# ESP32_with_USBC.net
KiCad netlist of a schematic drawn in Altium Designer
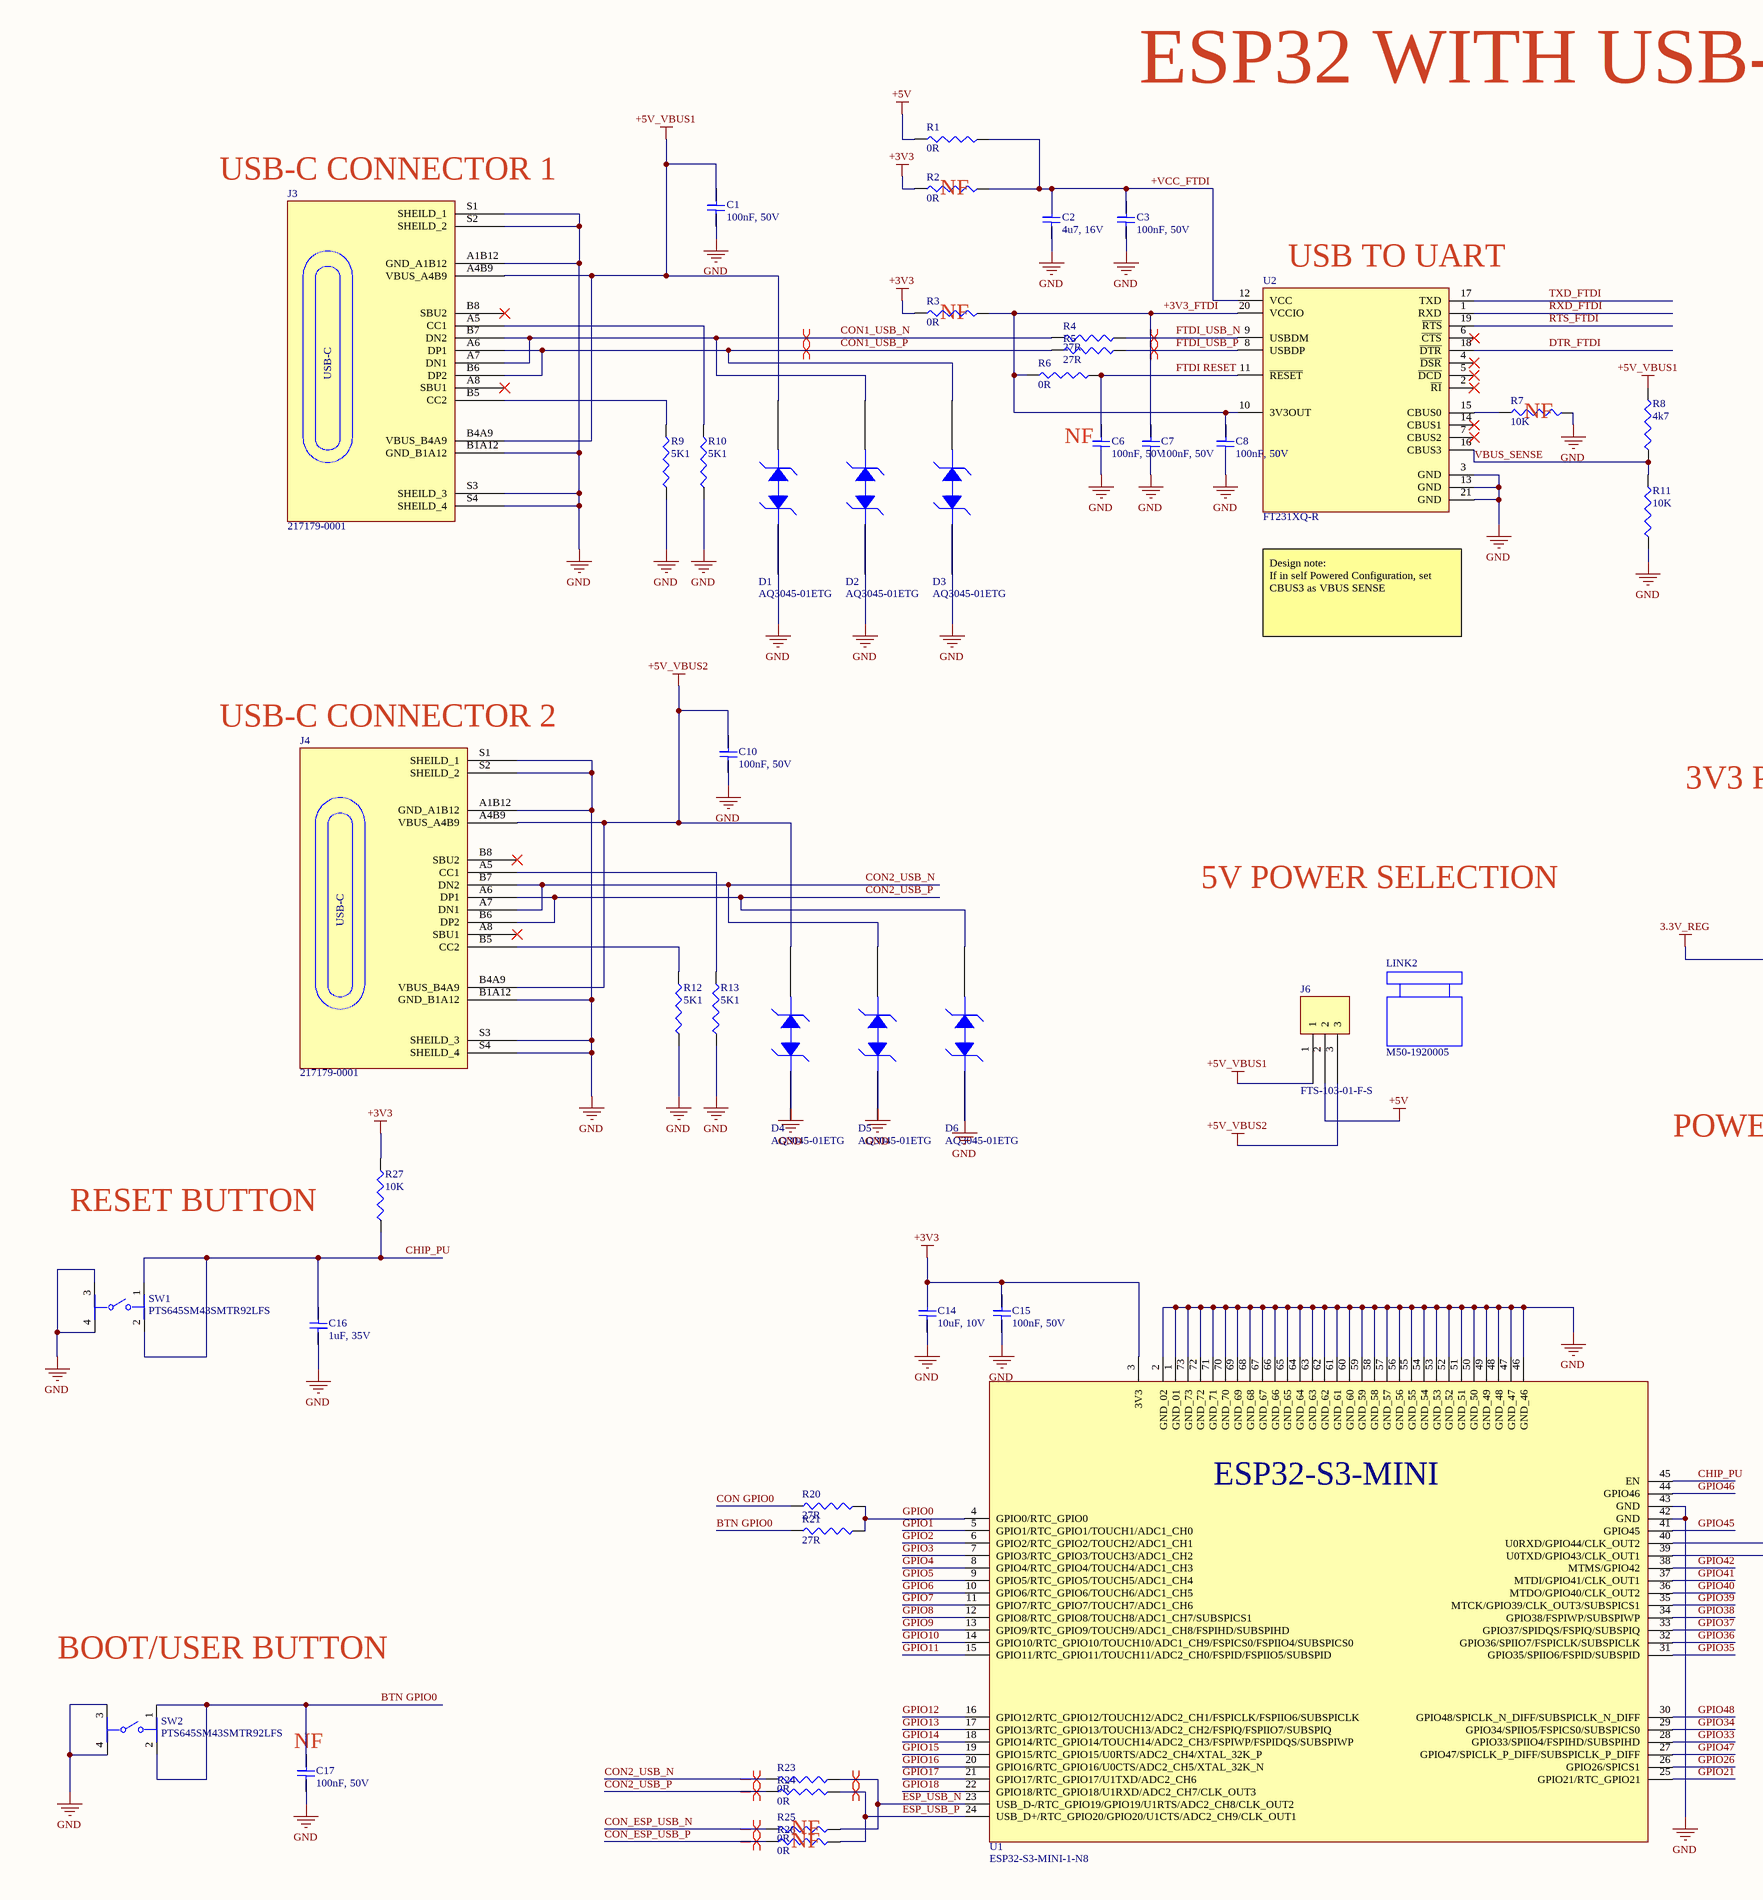
[diagram p0: ESP32 with USBC.SchDoc, left]
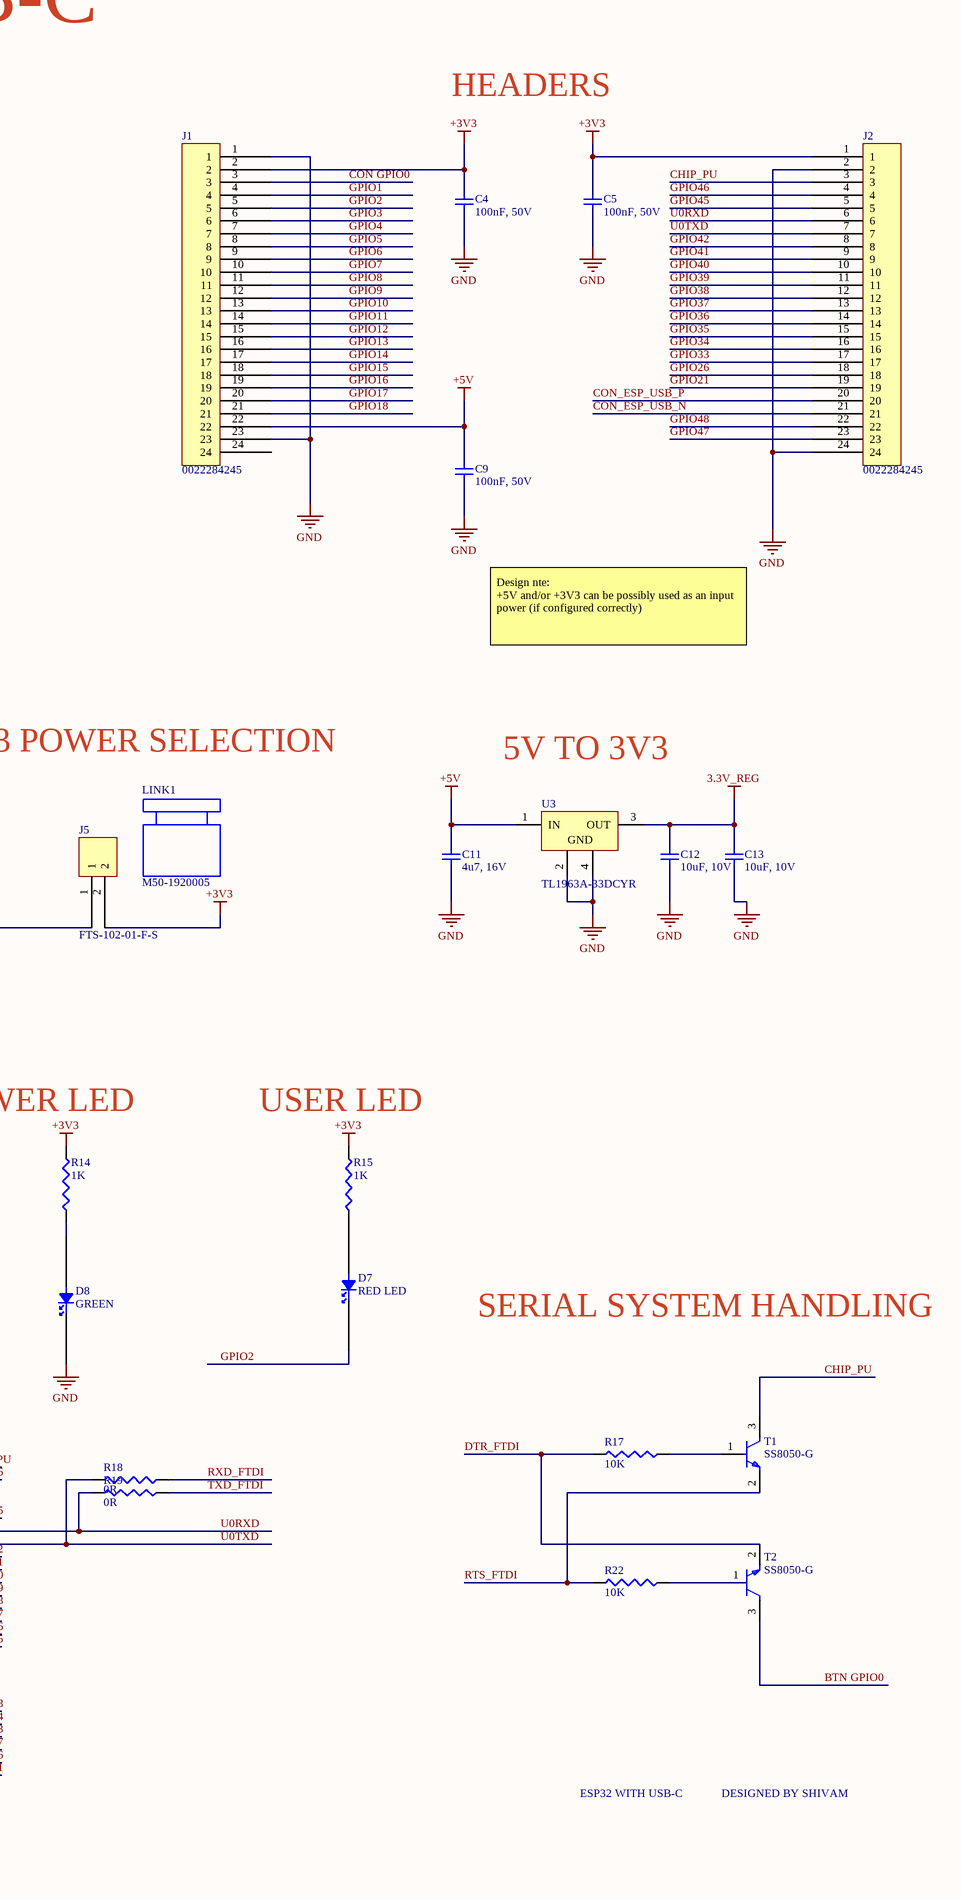
[diagram p1: ESP32 with USBC.SchDoc, right]

(export (version "E")
  (design (tool "Eeschema 10.0.6"))
  (components
    (comp (ref "C1")
      (value "100nF, 50V")
      (footprint "CAPC1005X55N")
      (description "CAP CER 0.1UF 50V X7R 0402")
      (fields
        (field (name "MANUFACTURER") "Samsung")
        (field (name "MANUFACTURER PART NUMBER") "CL05B104KB54PNC")
      )
      (libsource (lib "Schlib1") (part "CL05B104KB54PNC"))
    )
    (comp (ref "C2")
      (value "4u7, 16V")
      (footprint "CAPC1005X55N")
      (description "CAP CER 4.7UF 16V X5R 0402")
      (fields
        (field (name "MANUFACTURER") "Samsung")
        (field (name "MANUFACTURER PART NUMBER") "CL05A475MO5NUNC")
      )
      (libsource (lib "Schlib1") (part "CL05A475MO5NUNC"))
    )
    (comp (ref "C3")
      (value "100nF, 50V")
      (footprint "CAPC1005X55N")
      (description "CAP CER 0.1UF 50V X7R 0402")
      (fields
        (field (name "MANUFACTURER") "Samsung")
        (field (name "MANUFACTURER PART NUMBER") "CL05B104KB54PNC")
      )
      (libsource (lib "Schlib1") (part "CL05B104KB54PNC"))
    )
    (comp (ref "C4")
      (value "100nF, 50V")
      (footprint "CAPC1005X55N")
      (description "CAP CER 0.1UF 50V X7R 0402")
      (fields
        (field (name "MANUFACTURER") "Samsung")
        (field (name "MANUFACTURER PART NUMBER") "CL05B104KB54PNC")
      )
      (libsource (lib "Schlib1") (part "CL05B104KB54PNC"))
    )
    (comp (ref "C5")
      (value "100nF, 50V")
      (footprint "CAPC1005X55N")
      (description "CAP CER 0.1UF 50V X7R 0402")
      (fields
        (field (name "MANUFACTURER") "Samsung")
        (field (name "MANUFACTURER PART NUMBER") "CL05B104KB54PNC")
      )
      (libsource (lib "Schlib1") (part "CL05B104KB54PNC"))
    )
    (comp (ref "C6")
      (value "100nF, 50V")
      (footprint "CAPC1005X55N")
      (description "CAP CER 0.1UF 50V X7R 0402")
      (fields
        (field (name "MANUFACTURER") "Samsung")
        (field (name "MANUFACTURER PART NUMBER") "CL05B104KB54PNC")
      )
      (libsource (lib "Schlib1") (part "CL05B104KB54PNC"))
    )
    (comp (ref "C7")
      (value "100nF, 50V")
      (footprint "CAPC1005X55N")
      (description "CAP CER 0.1UF 50V X7R 0402")
      (fields
        (field (name "MANUFACTURER") "Samsung")
        (field (name "MANUFACTURER PART NUMBER") "CL05B104KB54PNC")
      )
      (libsource (lib "Schlib1") (part "CL05B104KB54PNC"))
    )
    (comp (ref "C8")
      (value "100nF, 50V")
      (footprint "CAPC1005X55N")
      (description "CAP CER 0.1UF 50V X7R 0402")
      (fields
        (field (name "MANUFACTURER") "Samsung")
        (field (name "MANUFACTURER PART NUMBER") "CL05B104KB54PNC")
      )
      (libsource (lib "Schlib1") (part "CL05B104KB54PNC"))
    )
    (comp (ref "C9")
      (value "100nF, 50V")
      (footprint "CAPC1005X55N")
      (description "CAP CER 0.1UF 50V X7R 0402")
      (fields
        (field (name "MANUFACTURER") "Samsung")
        (field (name "MANUFACTURER PART NUMBER") "CL05B104KB54PNC")
      )
      (libsource (lib "Schlib1") (part "CL05B104KB54PNC"))
    )
    (comp (ref "C10")
      (value "100nF, 50V")
      (footprint "CAPC1005X55N")
      (description "CAP CER 0.1UF 50V X7R 0402")
      (fields
        (field (name "MANUFACTURER") "Samsung")
        (field (name "MANUFACTURER PART NUMBER") "CL05B104KB54PNC")
      )
      (libsource (lib "Schlib1") (part "CL05B104KB54PNC"))
    )
    (comp (ref "C11")
      (value "4u7, 16V")
      (footprint "CAPC1005X55N")
      (description "CAP CER 4.7UF 16V X5R 0402")
      (fields
        (field (name "MANUFACTURER") "Samsung")
        (field (name "MANUFACTURER PART NUMBER") "CL05A475MO5NUNC")
      )
      (libsource (lib "Schlib1") (part "CL05A475MO5NUNC"))
    )
    (comp (ref "C12")
      (value "10uF, 10V")
      (footprint "CAPC1005X55N")
      (description "CAP CER 10UF 10V X5R 0402")
      (fields
        (field (name "MANUFACTURER") "Samsung")
        (field (name "MANUFACTURER PART NUMBER") "CL05A106MP8NUB8")
      )
      (libsource (lib "Schlib1") (part "CL05A106MP8NUB8"))
    )
    (comp (ref "C13")
      (value "10uF, 10V")
      (footprint "CAPC1005X55N")
      (description "CAP CER 10UF 10V X5R 0402")
      (fields
        (field (name "MANUFACTURER") "Samsung")
        (field (name "MANUFACTURER PART NUMBER") "CL05A106MP8NUB8")
      )
      (libsource (lib "Schlib1") (part "CL05A106MP8NUB8"))
    )
    (comp (ref "C14")
      (value "10uF, 10V")
      (footprint "CAPC1005X55N")
      (description "CAP CER 10UF 10V X5R 0402")
      (fields
        (field (name "MANUFACTURER") "Samsung")
        (field (name "MANUFACTURER PART NUMBER") "CL05A106MP8NUB8")
      )
      (libsource (lib "Schlib1") (part "CL05A106MP8NUB8"))
    )
    (comp (ref "C15")
      (value "100nF, 50V")
      (footprint "CAPC1005X55N")
      (description "CAP CER 0.1UF 50V X7R 0402")
      (fields
        (field (name "MANUFACTURER") "Samsung")
        (field (name "MANUFACTURER PART NUMBER") "CL05B104KB54PNC")
      )
      (libsource (lib "Schlib1") (part "CL05B104KB54PNC"))
    )
    (comp (ref "C16")
      (value "1uF, 35V")
      (footprint "CAPC1005X55N")
      (description "Cap Ceramic 1uF 35V X5R 0.25pF SMD 0402 85°C Cardboard T/R")
      (fields
        (field (name "MANUFACTURER") "Samsung")
        (field (name "MANUFACTURER PART NUMBER") "CL05A105KL5NRNC")
      )
      (libsource (lib "Schlib1") (part "CL05A105KL5NRNC"))
    )
    (comp (ref "C17")
      (value "100nF, 50V")
      (footprint "CAPC1005X55N")
      (description "CAP CER 0.1UF 50V X7R 0402")
      (fields
        (field (name "MANUFACTURER") "Samsung")
        (field (name "MANUFACTURER PART NUMBER") "CL05B104KB54PNC")
      )
      (libsource (lib "Schlib1") (part "CL05B104KB54PNC"))
    )
    (comp (ref "D1")
      (value "AQ3045-01ETG")
      (footprint "SOD882")
      (description "TVS DIODE 5.3VWM 12VC SOD882")
      (fields (field (name "MANUFACTURER") "Littelfuse") (field (name "LCSC PART NUMBER") "C3710326"))
      (libsource (lib "Schlib1") (part "AQ3045-01ETG"))
    )
    (comp (ref "D2")
      (value "AQ3045-01ETG")
      (footprint "SOD882")
      (description "TVS DIODE 5.3VWM 12VC SOD882")
      (fields (field (name "MANUFACTURER") "Littelfuse") (field (name "LCSC PART NUMBER") "C3710326"))
      (libsource (lib "Schlib1") (part "AQ3045-01ETG"))
    )
    (comp (ref "D3")
      (value "AQ3045-01ETG")
      (footprint "SOD882")
      (description "TVS DIODE 5.3VWM 12VC SOD882")
      (fields (field (name "MANUFACTURER") "Littelfuse") (field (name "LCSC PART NUMBER") "C3710326"))
      (libsource (lib "Schlib1") (part "AQ3045-01ETG"))
    )
    (comp (ref "D4")
      (value "AQ3045-01ETG")
      (footprint "SOD882")
      (description "TVS DIODE 5.3VWM 12VC SOD882")
      (fields (field (name "MANUFACTURER") "Littelfuse") (field (name "LCSC PART NUMBER") "C3710326"))
      (libsource (lib "Schlib1") (part "AQ3045-01ETG"))
    )
    (comp (ref "D5")
      (value "AQ3045-01ETG")
      (footprint "SOD882")
      (description "TVS DIODE 5.3VWM 12VC SOD882")
      (fields (field (name "MANUFACTURER") "Littelfuse") (field (name "LCSC PART NUMBER") "C3710326"))
      (libsource (lib "Schlib1") (part "AQ3045-01ETG"))
    )
    (comp (ref "D6")
      (value "AQ3045-01ETG")
      (footprint "SOD882")
      (description "TVS DIODE 5.3VWM 12VC SOD882")
      (fields (field (name "MANUFACTURER") "Littelfuse") (field (name "LCSC PART NUMBER") "C3710326"))
      (libsource (lib "Schlib1") (part "AQ3045-01ETG"))
    )
    (comp (ref "D7")
      (value "RED LED")
      (footprint "LED0402R")
      (description "LED RED 0402 SMD")
      (fields
        (field (name "MANUFACTURER") "Vishay")
        (field (name "MANUFACTURER PART NUMBER") "VLMS1500-GS08")
      )
      (libsource (lib "Schlib1") (part "VLMS1500-GS08"))
    )
    (comp (ref "D8")
      (value "GREEN")
      (footprint "LED0402G")
      (description "LED YLW-GRN 0402 SMD")
      (fields
        (field (name "MANUFACTURER") "Vishay")
        (field (name "MANUFACTURER PART NUMBER") "VLMG1500-GS08")
      )
      (libsource (lib "Schlib1") (part "VLMG1500-GS08"))
    )
    (comp (ref "J1")
      (value "0022284245")
      (footprint "HDR_1X24_2.54MM")
      (description "CONN HEADER VERT 24POS 2.54MM")
      (fields (field (name "MANUFACTURER") "Molex") (field (name "LCSC PART NUMBER") "C7145888"))
      (libsource (lib "") (part "0022284245_1"))
    )
    (comp (ref "J2")
      (value "0022284245")
      (footprint "HDR_1X24_2.54MM")
      (description "CONN HEADER VERT 24POS 2.54MM")
      (fields (field (name "MANUFACTURER") "Molex") (field (name "LCSC PART NUMBER") "C7145888"))
      (libsource (lib "Schlib1") (part "0022284245"))
    )
    (comp (ref "J3")
      (value "217179-0001")
      (footprint "FP-2171790001-MFG")
      (description "CONN RCP USB2.0 TYP C 24P SMD RA")
      (fields (field (name "MANUFACTURER") "Molex") (field (name "LCSC PART NUMBER") "C3197684"))
      (libsource (lib "Schlib1") (part "217179-0001"))
    )
    (comp (ref "J4")
      (value "217179-0001")
      (footprint "FP-2171790001-MFG")
      (description "CONN RCP USB2.0 TYP C 24P SMD RA")
      (fields (field (name "MANUFACTURER") "Molex") (field (name "LCSC PART NUMBER") "C3197684"))
      (libsource (lib "Schlib1") (part "217179-0001"))
    )
    (comp (ref "J5")
      (value "FTS-102-01-F-S")
      (footprint "HDR_1X2_1.27MM")
      (description "CONN HEADER VERT 2POS 1.27MM")
      (fields (field (name "MANUFACTURER") "Samtec") (field (name "LCSC PART NUMBER") "C6045317"))
      (libsource (lib "Schlib1") (part "FTS-102-01-F-S"))
    )
    (comp (ref "J6")
      (value "FTS-103-01-F-S")
      (footprint "HDR_1X3_1.27MM")
      (description "CONN HEADER VERT 3POS 1.27MM")
      (fields (field (name "MANUFACTURER") "Samtec"))
      (libsource (lib "Schlib1") (part "FTS-103-01-F-S"))
    )
    (comp (ref "LINK1")
      (value "M50-1920005")
      (description "CONN SHUNT 1.27MM RED")
      (fields (field (name "MANUFACTURER") "Harwin"))
      (libsource (lib "Schlib1") (part "M50-1920005"))
    )
    (comp (ref "LINK2")
      (value "M50-1920005")
      (description "CONN SHUNT 1.27MM RED")
      (fields (field (name "MANUFACTURER") "Harwin"))
      (libsource (lib "Schlib1") (part "M50-1920005"))
    )
    (comp (ref "R1")
      (value "0R")
      (footprint "RESC1005X37N")
      (description "Metal Glaze/thick Film, 0.0625W, 0ohm, Surface Mount, 0402")
      (fields
        (field (name "MANUFACTURER") "Yageo")
        (field (name "MANUFACTURER PART NUMBER") "RC0402JR-070RL")
      )
      (libsource (lib "Schlib1") (part "RC0402JR-070RL"))
    )
    (comp (ref "R2")
      (value "0R")
      (footprint "RESC1005X37N")
      (description "Metal Glaze/thick Film, 0.0625W, 0ohm, Surface Mount, 0402")
      (fields
        (field (name "MANUFACTURER") "Yageo")
        (field (name "MANUFACTURER PART NUMBER") "RC0402JR-070RL")
      )
      (libsource (lib "Schlib1") (part "RC0402JR-070RL"))
    )
    (comp (ref "R3")
      (value "0R")
      (footprint "RESC1005X37N")
      (description "Metal Glaze/thick Film, 0.0625W, 0ohm, Surface Mount, 0402")
      (fields
        (field (name "MANUFACTURER") "Yageo")
        (field (name "MANUFACTURER PART NUMBER") "RC0402JR-070RL")
      )
      (libsource (lib "Schlib1") (part "RC0402JR-070RL"))
    )
    (comp (ref "R4")
      (value "27R")
      (footprint "RESC1005X37N")
      (description "RES SMD 27 OHM 0.1% 1/16W 0402")
      (fields
        (field (name "MANUFACTURER") "Yageo")
        (field (name "MANUFACTURER PART NUMBER") "RT0402BRD0727RL")
      )
      (libsource (lib "Schlib1") (part "RT0402BRD0727RL"))
    )
    (comp (ref "R5")
      (value "27R")
      (footprint "RESC1005X37N")
      (description "RES SMD 27 OHM 0.1% 1/16W 0402")
      (fields
        (field (name "MANUFACTURER") "Yageo")
        (field (name "MANUFACTURER PART NUMBER") "RT0402BRD0727RL")
      )
      (libsource (lib "Schlib1") (part "RT0402BRD0727RL"))
    )
    (comp (ref "R6")
      (value "0R")
      (footprint "RESC1005X37N")
      (description "Metal Glaze/thick Film, 0.0625W, 0ohm, Surface Mount, 0402")
      (fields
        (field (name "MANUFACTURER") "Yageo")
        (field (name "MANUFACTURER PART NUMBER") "RC0402JR-070RL")
      )
      (libsource (lib "Schlib1") (part "RC0402JR-070RL"))
    )
    (comp (ref "R7")
      (value "10K")
      (footprint "RESC1005X37N")
      (description "RES SMD 10K OHM 1% 1/16W 0402")
      (fields
        (field (name "MANUFACTURER") "Yageo")
        (field (name "MANUFACTURER PART NUMBER") "AC0402FR-0710KL")
      )
      (libsource (lib "Schlib1") (part "AC0402FR-0710KL"))
    )
    (comp (ref "R8")
      (value "4k7")
      (footprint "RESC1005X37N")
      (description "RES 4.7K OHM 1% 1/16W 0402")
      (fields
        (field (name "MANUFACTURER") "Yageo")
        (field (name "MANUFACTURER PART NUMBER") "RC0402FR-074K7L")
      )
      (libsource (lib "Schlib1") (part "RC0402FR-074K7L"))
    )
    (comp (ref "R9")
      (value "5K1")
      (footprint "RESC1005X37N")
      (description "RES SMD 5.1K OHM 1% 1/16W 0402")
      (fields
        (field (name "MANUFACTURER") "Yageo")
        (field (name "MANUFACTURER PART NUMBER") "AC0402FR-075K1L")
      )
      (libsource (lib "Schlib1") (part "AC0402FR-075K1L"))
    )
    (comp (ref "R10")
      (value "5K1")
      (footprint "RESC1005X37N")
      (description "RES SMD 5.1K OHM 1% 1/16W 0402")
      (fields
        (field (name "MANUFACTURER") "Yageo")
        (field (name "MANUFACTURER PART NUMBER") "AC0402FR-075K1L")
      )
      (libsource (lib "Schlib1") (part "AC0402FR-075K1L"))
    )
    (comp (ref "R11")
      (value "10K")
      (footprint "RESC1005X37N")
      (description "RES SMD 10K OHM 1% 1/16W 0402")
      (fields
        (field (name "MANUFACTURER") "Yageo")
        (field (name "MANUFACTURER PART NUMBER") "AC0402FR-0710KL")
      )
      (libsource (lib "Schlib1") (part "AC0402FR-0710KL"))
    )
    (comp (ref "R12")
      (value "5K1")
      (footprint "RESC1005X37N")
      (description "RES SMD 5.1K OHM 1% 1/16W 0402")
      (fields
        (field (name "MANUFACTURER") "Yageo")
        (field (name "MANUFACTURER PART NUMBER") "AC0402FR-075K1L")
      )
      (libsource (lib "Schlib1") (part "AC0402FR-075K1L"))
    )
    (comp (ref "R13")
      (value "5K1")
      (footprint "RESC1005X37N")
      (description "RES SMD 5.1K OHM 1% 1/16W 0402")
      (fields
        (field (name "MANUFACTURER") "Yageo")
        (field (name "MANUFACTURER PART NUMBER") "AC0402FR-075K1L")
      )
      (libsource (lib "Schlib1") (part "AC0402FR-075K1L"))
    )
    (comp (ref "R14")
      (value "1K")
      (footprint "RESC1005X37N")
      (description "RES 1K OHM 1% 1/16W 0402")
      (fields
        (field (name "MANUFACTURER") "Yageo")
        (field (name "MANUFACTURER PART NUMBER") "RC0402FR-071KL")
      )
      (libsource (lib "Schlib1") (part "RC0402FR-071KL"))
    )
    (comp (ref "R15")
      (value "1K")
      (footprint "RESC1005X37N")
      (description "RES 1K OHM 1% 1/16W 0402")
      (fields
        (field (name "MANUFACTURER") "Yageo")
        (field (name "MANUFACTURER PART NUMBER") "RC0402FR-071KL")
      )
      (libsource (lib "Schlib1") (part "RC0402FR-071KL"))
    )
    (comp (ref "R17")
      (value "10K")
      (footprint "RESC1005X37N")
      (description "RES SMD 10K OHM 1% 1/16W 0402")
      (fields
        (field (name "MANUFACTURER") "Yageo")
        (field (name "MANUFACTURER PART NUMBER") "AC0402FR-0710KL")
      )
      (libsource (lib "Schlib1") (part "AC0402FR-0710KL"))
    )
    (comp (ref "R18")
      (value "0R")
      (footprint "RESC1005X37N")
      (description "Metal Glaze/thick Film, 0.0625W, 0ohm, Surface Mount, 0402")
      (fields
        (field (name "MANUFACTURER") "Yageo")
        (field (name "MANUFACTURER PART NUMBER") "RC0402JR-070RL")
      )
      (libsource (lib "Schlib1") (part "RC0402JR-070RL"))
    )
    (comp (ref "R19")
      (value "0R")
      (footprint "RESC1005X37N")
      (description "Metal Glaze/thick Film, 0.0625W, 0ohm, Surface Mount, 0402")
      (fields
        (field (name "MANUFACTURER") "Yageo")
        (field (name "MANUFACTURER PART NUMBER") "RC0402JR-070RL")
      )
      (libsource (lib "Schlib1") (part "RC0402JR-070RL"))
    )
    (comp (ref "R20")
      (value "27R")
      (footprint "RESC1005X37N")
      (description "RES SMD 27 OHM 0.1% 1/16W 0402")
      (fields
        (field (name "MANUFACTURER") "Yageo")
        (field (name "MANUFACTURER PART NUMBER") "RT0402BRD0727RL")
      )
      (libsource (lib "Schlib1") (part "RT0402BRD0727RL"))
    )
    (comp (ref "R21")
      (value "27R")
      (footprint "RESC1005X37N")
      (description "RES SMD 27 OHM 0.1% 1/16W 0402")
      (fields
        (field (name "MANUFACTURER") "Yageo")
        (field (name "MANUFACTURER PART NUMBER") "RT0402BRD0727RL")
      )
      (libsource (lib "Schlib1") (part "RT0402BRD0727RL"))
    )
    (comp (ref "R22")
      (value "10K")
      (footprint "RESC1005X37N")
      (description "RES SMD 10K OHM 1% 1/16W 0402")
      (fields
        (field (name "MANUFACTURER") "Yageo")
        (field (name "MANUFACTURER PART NUMBER") "AC0402FR-0710KL")
      )
      (libsource (lib "Schlib1") (part "AC0402FR-0710KL"))
    )
    (comp (ref "R23")
      (value "0R")
      (footprint "RESC1005X37N")
      (description "Metal Glaze/thick Film, 0.0625W, 0ohm, Surface Mount, 0402")
      (fields
        (field (name "MANUFACTURER") "Yageo")
        (field (name "MANUFACTURER PART NUMBER") "RC0402JR-070RL")
      )
      (libsource (lib "Schlib1") (part "RC0402JR-070RL"))
    )
    (comp (ref "R24")
      (value "0R")
      (footprint "RESC1005X37N")
      (description "Metal Glaze/thick Film, 0.0625W, 0ohm, Surface Mount, 0402")
      (fields
        (field (name "MANUFACTURER") "Yageo")
        (field (name "MANUFACTURER PART NUMBER") "RC0402JR-070RL")
      )
      (libsource (lib "Schlib1") (part "RC0402JR-070RL"))
    )
    (comp (ref "R25")
      (value "0R")
      (footprint "RESC1005X37N")
      (description "Metal Glaze/thick Film, 0.0625W, 0ohm, Surface Mount, 0402")
      (fields
        (field (name "MANUFACTURER") "Yageo")
        (field (name "MANUFACTURER PART NUMBER") "RC0402JR-070RL")
      )
      (libsource (lib "Schlib1") (part "RC0402JR-070RL"))
    )
    (comp (ref "R26")
      (value "0R")
      (footprint "RESC1005X37N")
      (description "Metal Glaze/thick Film, 0.0625W, 0ohm, Surface Mount, 0402")
      (fields
        (field (name "MANUFACTURER") "Yageo")
        (field (name "MANUFACTURER PART NUMBER") "RC0402JR-070RL")
      )
      (libsource (lib "Schlib1") (part "RC0402JR-070RL"))
    )
    (comp (ref "R27")
      (value "10K")
      (footprint "RESC1005X37N")
      (description "RES SMD 10K OHM 1% 1/16W 0402")
      (fields
        (field (name "MANUFACTURER") "Yageo")
        (field (name "MANUFACTURER PART NUMBER") "AC0402FR-0710KL")
      )
      (libsource (lib "Schlib1") (part "AC0402FR-0710KL"))
    )
    (comp (ref "SW1")
      (value "PTS645SM43SMTR92LFS")
      (footprint "FP-PTS645SM43SMTR92LFS-MFG")
      (description "SWITCH TACTILE SPST-NO 0.05A 12V")
      (fields (field (name "MANUFACTURER") "ITT C&K") (field (name "LCSC PART NUMBER") "C221880"))
      (libsource (lib "Schlib1") (part "PTS645SM43SMTR92LFS"))
    )
    (comp (ref "SW2")
      (value "PTS645SM43SMTR92LFS")
      (footprint "FP-PTS645SM43SMTR92LFS-MFG")
      (description "SWITCH TACTILE SPST-NO 0.05A 12V")
      (fields (field (name "MANUFACTURER") "ITT C&K") (field (name "LCSC PART NUMBER") "C221880"))
      (libsource (lib "Schlib1") (part "PTS645SM43SMTR92LFS"))
    )
    (comp (ref "T1")
      (value "SS8050-G")
      (footprint "FP-SS8050-G-IPC_B")
      (description "TRANS NPN 25V 1.5A SOT23-3")
      (fields (field (name "MANUFACTURER") "Comchip") (field (name "LCSC PART NUMBER") "C164886"))
      (libsource (lib "") (part "SS8050-G_1"))
    )
    (comp (ref "T2")
      (value "SS8050-G")
      (footprint "FP-SS8050-G-IPC_B")
      (description "TRANS NPN 25V 1.5A SOT23-3")
      (fields (field (name "MANUFACTURER") "Comchip") (field (name "LCSC PART NUMBER") "C164886"))
      (libsource (lib "Schlib1") (part "SS8050-G"))
    )
    (comp (ref "U1")
      (value "ESP32-S3-MINI-1-N8")
      (footprint "XCVR_ESP32-S3-MINI-1-N8")
      (description "SMD module, ESP32-S3FN8, 8 MB SPI flash, PCB antenna")
      (fields (field (name "MANUFACTURER") "Espressif Systems") (field (name "LCSC PART NUMBER") "C2913206"))
      (libsource (lib "Schlib1") (part "ESP32-S3-MINI-1-N8"))
    )
    (comp (ref "U2")
      (value "FT231XQ-R")
      (footprint "FP-QFN-20-IPC_B")
      (description "IC USB SERIAL FULL UART 20QFN")
      (fields (field (name "MANUFACTURER") "FTDI") (field (name "LCSC PART NUMBER") "C132159"))
      (libsource (lib "Schlib1") (part "FT231XQ-R"))
    )
    (comp (ref "U3")
      (value "TL1963A-33DCYR")
      (footprint "DCY0004A_M")
      (description "IC REG LINEAR 3.3V 1.5A SOT223-4")
      (fields (field (name "MANUFACTURER") "Texas Instruments") (field (name "LCSC PART NUMBER") "C181262"))
      (libsource (lib "Schlib1") (part "TL1963A-33DCYR"))
    )
  )
  (nets
    (net (code "1") (name "+3V3") (class "Default")
      (node (ref "C14") (pin "2") (pinfunction "2_2") (pintype "passive"))
      (node (ref "C15") (pin "2") (pinfunction "2_2") (pintype "passive"))
      (node (ref "C4") (pin "2") (pinfunction "2_2") (pintype "passive"))
      (node (ref "C5") (pin "2") (pinfunction "2_2") (pintype "passive"))
      (node (ref "J1") (pin "2") (pinfunction "2_2") (pintype "passive"))
      (node (ref "J2") (pin "1") (pinfunction "1_1") (pintype "passive"))
      (node (ref "J5") (pin "2") (pinfunction "2_2") (pintype "passive"))
      (node (ref "R14") (pin "2") (pinfunction "2_2") (pintype "passive"))
      (node (ref "R15") (pin "2") (pinfunction "2_2") (pintype "passive"))
      (node (ref "R2") (pin "1") (pinfunction "1_1") (pintype "passive"))
      (node (ref "R27") (pin "2") (pinfunction "2_2") (pintype "passive"))
      (node (ref "R3") (pin "1") (pinfunction "1_1") (pintype "passive"))
      (node (ref "U1") (pin "3") (pinfunction "3V3_3") (pintype "passive"))
    )
    (net (code "2") (name "+5V") (class "Default")
      (node (ref "C11") (pin "2") (pinfunction "2_2") (pintype "passive"))
      (node (ref "C9") (pin "2") (pinfunction "2_2") (pintype "passive"))
      (node (ref "J1") (pin "22") (pinfunction "22_22") (pintype "passive"))
      (node (ref "J6") (pin "2") (pinfunction "2_2") (pintype "passive"))
      (node (ref "R1") (pin "1") (pinfunction "1_1") (pintype "passive"))
      (node (ref "U3") (pin "1") (pinfunction "IN_1") (pintype "power_in"))
    )
    (net (code "3") (name "+5V_VBUS1") (class "Default")
      (node (ref "C1") (pin "2") (pinfunction "2_2") (pintype "passive"))
      (node (ref "D1") (pin "1") (pinfunction "1_1") (pintype "passive"))
      (node (ref "J3") (pin "A4B9") (pinfunction "VBUS_A4B9_A4B9") (pintype "passive"))
      (node (ref "J3") (pin "B4A9") (pinfunction "VBUS_B4A9_B4A9") (pintype "passive"))
      (node (ref "J6") (pin "1") (pinfunction "1_1") (pintype "passive"))
      (node (ref "R8") (pin "2") (pinfunction "2_2") (pintype "passive"))
    )
    (net (code "4") (name "+5V_VBUS2") (class "Default")
      (node (ref "C10") (pin "2") (pinfunction "2_2") (pintype "passive"))
      (node (ref "D4") (pin "1") (pinfunction "1_1") (pintype "passive"))
      (node (ref "J4") (pin "A4B9") (pinfunction "VBUS_A4B9_A4B9") (pintype "passive"))
      (node (ref "J4") (pin "B4A9") (pinfunction "VBUS_B4A9_B4A9") (pintype "passive"))
      (node (ref "J6") (pin "3") (pinfunction "3_3") (pintype "passive"))
    )
    (net (code "5") (name "/+3V3_FTDI") (class "Default")
      (node (ref "C7") (pin "2") (pinfunction "2_2") (pintype "passive"))
      (node (ref "C8") (pin "2") (pinfunction "2_2") (pintype "passive"))
      (node (ref "R3") (pin "2") (pinfunction "2_2") (pintype "passive"))
      (node (ref "R6") (pin "1") (pinfunction "1_1") (pintype "passive"))
      (node (ref "U2") (pin "10") (pinfunction "3V3OUT_10") (pintype "passive"))
      (node (ref "U2") (pin "20") (pinfunction "VCCIO_20") (pintype "passive"))
    )
    (net (code "6") (name "/+VCC_FTDI") (class "Default")
      (node (ref "C2") (pin "2") (pinfunction "2_2") (pintype "passive"))
      (node (ref "C3") (pin "2") (pinfunction "2_2") (pintype "passive"))
      (node (ref "R1") (pin "2") (pinfunction "2_2") (pintype "passive"))
      (node (ref "R2") (pin "2") (pinfunction "2_2") (pintype "passive"))
      (node (ref "U2") (pin "12") (pinfunction "VCC_12") (pintype "passive"))
    )
    (net (code "7") (name "/BTN GPIO0") (class "Default")
      (node (ref "C17") (pin "2") (pinfunction "2_2") (pintype "passive"))
      (node (ref "R21") (pin "1") (pinfunction "1_1") (pintype "passive"))
      (node (ref "SW2") (pin "1") (pinfunction "1_1") (pintype "passive"))
      (node (ref "SW2") (pin "2") (pinfunction "2_2") (pintype "passive"))
      (node (ref "T2") (pin "3") (pinfunction "C_3") (pintype "passive"))
    )
    (net (code "8") (name "/CHIP_PU") (class "Default")
      (node (ref "C16") (pin "1") (pinfunction "1_1") (pintype "passive"))
      (node (ref "J2") (pin "3") (pinfunction "3_3") (pintype "passive"))
      (node (ref "R27") (pin "1") (pinfunction "1_1") (pintype "passive"))
      (node (ref "SW1") (pin "1") (pinfunction "1_1") (pintype "passive"))
      (node (ref "SW1") (pin "2") (pinfunction "2_2") (pintype "passive"))
      (node (ref "T1") (pin "3") (pinfunction "C_3") (pintype "passive"))
      (node (ref "U1") (pin "45") (pinfunction "EN_45") (pintype "passive"))
    )
    (net (code "9") (name "/CON GPIO0") (class "Default")
      (node (ref "J1") (pin "3") (pinfunction "3_3") (pintype "passive"))
      (node (ref "R20") (pin "1") (pinfunction "1_1") (pintype "passive"))
    )
    (net (code "10") (name "/CON1_USB_N") (class "Default")
      (node (ref "D2") (pin "1") (pinfunction "1_1") (pintype "passive"))
      (node (ref "J3") (pin "A7") (pinfunction "DN1_A7") (pintype "passive"))
      (node (ref "J3") (pin "B7") (pinfunction "DN2_B7") (pintype "passive"))
      (node (ref "R4") (pin "1") (pinfunction "1_1") (pintype "passive"))
    )
    (net (code "11") (name "/CON1_USB_P") (class "Default")
      (node (ref "D3") (pin "1") (pinfunction "1_1") (pintype "passive"))
      (node (ref "J3") (pin "A6") (pinfunction "DP1_A6") (pintype "passive"))
      (node (ref "J3") (pin "B6") (pinfunction "DP2_B6") (pintype "passive"))
      (node (ref "R5") (pin "1") (pinfunction "1_1") (pintype "passive"))
    )
    (net (code "12") (name "/CON2_USB_N") (class "Default")
      (node (ref "D5") (pin "1") (pinfunction "1_1") (pintype "passive"))
      (node (ref "J4") (pin "A7") (pinfunction "DN1_A7") (pintype "passive"))
      (node (ref "J4") (pin "B7") (pinfunction "DN2_B7") (pintype "passive"))
      (node (ref "R23") (pin "1") (pinfunction "1_1") (pintype "passive"))
    )
    (net (code "13") (name "/CON2_USB_P") (class "Default")
      (node (ref "D6") (pin "1") (pinfunction "1_1") (pintype "passive"))
      (node (ref "J4") (pin "A6") (pinfunction "DP1_A6") (pintype "passive"))
      (node (ref "J4") (pin "B6") (pinfunction "DP2_B6") (pintype "passive"))
      (node (ref "R24") (pin "1") (pinfunction "1_1") (pintype "passive"))
    )
    (net (code "14") (name "/CON_ESP_USB_N") (class "Default")
      (node (ref "J2") (pin "21") (pinfunction "21_21") (pintype "passive"))
      (node (ref "R25") (pin "1") (pinfunction "1_1") (pintype "passive"))
    )
    (net (code "15") (name "/CON_ESP_USB_P") (class "Default")
      (node (ref "J2") (pin "20") (pinfunction "20_20") (pintype "passive"))
      (node (ref "R26") (pin "1") (pinfunction "1_1") (pintype "passive"))
    )
    (net (code "16") (name "/DTR_FTDI") (class "Default")
      (node (ref "R17") (pin "2") (pinfunction "2_2") (pintype "passive"))
      (node (ref "T2") (pin "2") (pinfunction "E_2") (pintype "passive"))
      (node (ref "U2") (pin "18") (pinfunction "~{DTR}_18") (pintype "passive"))
    )
    (net (code "17") (name "/ESP_USB_N") (class "Default")
      (node (ref "R23") (pin "2") (pinfunction "2_2") (pintype "passive"))
      (node (ref "R25") (pin "2") (pinfunction "2_2") (pintype "passive"))
      (node (ref "U1") (pin "23") (pinfunction "USB_D-/RTC_GPIO19/GPIO19/U1RTS/ADC2_CH8/CLK_OUT2_23") (pintype "passive"))
    )
    (net (code "18") (name "/ESP_USB_P") (class "Default")
      (node (ref "R24") (pin "2") (pinfunction "2_2") (pintype "passive"))
      (node (ref "R26") (pin "2") (pinfunction "2_2") (pintype "passive"))
      (node (ref "U1") (pin "24") (pinfunction "USB_D+/RTC_GPIO20/GPIO20/U1CTS/ADC2_CH9/CLK_OUT1_24") (pintype "passive"))
    )
    (net (code "19") (name "/FTDI RESET") (class "Default")
      (node (ref "C6") (pin "2") (pinfunction "2_2") (pintype "passive"))
      (node (ref "R6") (pin "2") (pinfunction "2_2") (pintype "passive"))
      (node (ref "U2") (pin "11") (pinfunction "~{RESET}_11") (pintype "passive"))
    )
    (net (code "20") (name "/FTDI_USB_N") (class "Default")
      (node (ref "R4") (pin "2") (pinfunction "2_2") (pintype "passive"))
      (node (ref "U2") (pin "9") (pinfunction "USBDM_9") (pintype "passive"))
    )
    (net (code "21") (name "/FTDI_USB_P") (class "Default")
      (node (ref "R5") (pin "2") (pinfunction "2_2") (pintype "passive"))
      (node (ref "U2") (pin "8") (pinfunction "USBDP_8") (pintype "passive"))
    )
    (net (code "22") (name "/GPIO0") (class "Default")
      (node (ref "R20") (pin "2") (pinfunction "2_2") (pintype "passive"))
      (node (ref "R21") (pin "2") (pinfunction "2_2") (pintype "passive"))
      (node (ref "U1") (pin "4") (pinfunction "GPIO0/RTC_GPIO0_4") (pintype "passive"))
    )
    (net (code "23") (name "/GPIO1") (class "Default")
      (node (ref "J1") (pin "4") (pinfunction "4_4") (pintype "passive"))
      (node (ref "U1") (pin "5") (pinfunction "GPIO1/RTC_GPIO1/TOUCH1/ADC1_CH0_5") (pintype "passive"))
    )
    (net (code "24") (name "/GPIO2") (class "Default")
      (node (ref "D7") (pin "1") (pinfunction "1_1") (pintype "passive"))
      (node (ref "J1") (pin "5") (pinfunction "5_5") (pintype "passive"))
      (node (ref "U1") (pin "6") (pinfunction "GPIO2/RTC_GPIO2/TOUCH2/ADC1_CH1_6") (pintype "passive"))
    )
    (net (code "25") (name "/GPIO3") (class "Default")
      (node (ref "J1") (pin "6") (pinfunction "6_6") (pintype "passive"))
      (node (ref "U1") (pin "7") (pinfunction "GPIO3/RTC_GPIO3/TOUCH3/ADC1_CH2_7") (pintype "passive"))
    )
    (net (code "26") (name "/GPIO4") (class "Default")
      (node (ref "J1") (pin "7") (pinfunction "7_7") (pintype "passive"))
      (node (ref "U1") (pin "8") (pinfunction "GPIO4/RTC_GPIO4/TOUCH4/ADC1_CH3_8") (pintype "passive"))
    )
    (net (code "27") (name "/GPIO5") (class "Default")
      (node (ref "J1") (pin "8") (pinfunction "8_8") (pintype "passive"))
      (node (ref "U1") (pin "9") (pinfunction "GPIO5/RTC_GPIO5/TOUCH5/ADC1_CH4_9") (pintype "passive"))
    )
    (net (code "28") (name "/GPIO6") (class "Default")
      (node (ref "J1") (pin "9") (pinfunction "9_9") (pintype "passive"))
      (node (ref "U1") (pin "10") (pinfunction "GPIO6/RTC_GPIO6/TOUCH6/ADC1_CH5_10") (pintype "passive"))
    )
    (net (code "29") (name "/GPIO7") (class "Default")
      (node (ref "J1") (pin "10") (pinfunction "10_10") (pintype "passive"))
      (node (ref "U1") (pin "11") (pinfunction "GPIO7/RTC_GPIO7/TOUCH7/ADC1_CH6_11") (pintype "passive"))
    )
    (net (code "30") (name "/GPIO8") (class "Default")
      (node (ref "J1") (pin "11") (pinfunction "11_11") (pintype "passive"))
      (node (ref "U1") (pin "12") (pinfunction "GPIO8/RTC_GPIO8/TOUCH8/ADC1_CH7/SUBSPICS1_12") (pintype "passive"))
    )
    (net (code "31") (name "/GPIO9") (class "Default")
      (node (ref "J1") (pin "12") (pinfunction "12_12") (pintype "passive"))
      (node (ref "U1") (pin "13") (pinfunction "GPIO9/RTC_GPIO9/TOUCH9/ADC1_CH8/FSPIHD/SUBSPIHD_13") (pintype "passive"))
    )
    (net (code "32") (name "/GPIO10") (class "Default")
      (node (ref "J1") (pin "13") (pinfunction "13_13") (pintype "passive"))
      (node (ref "U1") (pin "14") (pinfunction "GPIO10/RTC_GPIO10/TOUCH10/ADC1_CH9/FSPICS0/FSPIIO4/SUBSPICS0_14") (pintype "passive"))
    )
    (net (code "33") (name "/GPIO11") (class "Default")
      (node (ref "J1") (pin "14") (pinfunction "14_14") (pintype "passive"))
      (node (ref "U1") (pin "15") (pinfunction "GPIO11/RTC_GPIO11/TOUCH11/ADC2_CH0/FSPID/FSPIIO5/SUBSPID_15") (pintype "passive"))
    )
    (net (code "34") (name "/GPIO12") (class "Default")
      (node (ref "J1") (pin "15") (pinfunction "15_15") (pintype "passive"))
      (node (ref "U1") (pin "16") (pinfunction "GPIO12/RTC_GPIO12/TOUCH12/ADC2_CH1/FSPICLK/FSPIIO6/SUBSPICLK_16") (pintype "passive"))
    )
    (net (code "35") (name "/GPIO13") (class "Default")
      (node (ref "J1") (pin "16") (pinfunction "16_16") (pintype "passive"))
      (node (ref "U1") (pin "17") (pinfunction "GPIO13/RTC_GPIO13/TOUCH13/ADC2_CH2/FSPIQ/FSPIIO7/SUBSPIQ_17") (pintype "passive"))
    )
    (net (code "36") (name "/GPIO14") (class "Default")
      (node (ref "J1") (pin "17") (pinfunction "17_17") (pintype "passive"))
      (node (ref "U1") (pin "18") (pinfunction "GPIO14/RTC_GPIO14/TOUCH14/ADC2_CH3/FSPIWP/FSPIDQS/SUBSPIWP_18") (pintype "passive"))
    )
    (net (code "37") (name "/GPIO15") (class "Default")
      (node (ref "J1") (pin "18") (pinfunction "18_18") (pintype "passive"))
      (node (ref "U1") (pin "19") (pinfunction "GPIO15/RTC_GPIO15/U0RTS/ADC2_CH4/XTAL_32K_P_19") (pintype "passive"))
    )
    (net (code "38") (name "/GPIO16") (class "Default")
      (node (ref "J1") (pin "19") (pinfunction "19_19") (pintype "passive"))
      (node (ref "U1") (pin "20") (pinfunction "GPIO16/RTC_GPIO16/U0CTS/ADC2_CH5/XTAL_32K_N_20") (pintype "passive"))
    )
    (net (code "39") (name "/GPIO17") (class "Default")
      (node (ref "J1") (pin "20") (pinfunction "20_20") (pintype "passive"))
      (node (ref "U1") (pin "21") (pinfunction "GPIO17/RTC_GPIO17/U1TXD/ADC2_CH6_21") (pintype "passive"))
    )
    (net (code "40") (name "/GPIO18") (class "Default")
      (node (ref "J1") (pin "21") (pinfunction "21_21") (pintype "passive"))
      (node (ref "U1") (pin "22") (pinfunction "GPIO18/RTC_GPIO18/U1RXD/ADC2_CH7/CLK_OUT3_22") (pintype "passive"))
    )
    (net (code "41") (name "/GPIO21") (class "Default")
      (node (ref "J2") (pin "19") (pinfunction "19_19") (pintype "passive"))
      (node (ref "U1") (pin "25") (pinfunction "GPIO21/RTC_GPIO21_25") (pintype "passive"))
    )
    (net (code "42") (name "/GPIO26") (class "Default")
      (node (ref "J2") (pin "18") (pinfunction "18_18") (pintype "passive"))
      (node (ref "U1") (pin "26") (pinfunction "GPIO26/SPICS1_26") (pintype "passive"))
    )
    (net (code "43") (name "/GPIO33") (class "Default")
      (node (ref "J2") (pin "17") (pinfunction "17_17") (pintype "passive"))
      (node (ref "U1") (pin "28") (pinfunction "GPIO33/SPIIO4/FSPIHD/SUBSPIHD_28") (pintype "passive"))
    )
    (net (code "44") (name "/GPIO34") (class "Default")
      (node (ref "J2") (pin "16") (pinfunction "16_16") (pintype "passive"))
      (node (ref "U1") (pin "29") (pinfunction "GPIO34/SPIIO5/FSPICS0/SUBSPICS0_29") (pintype "passive"))
    )
    (net (code "45") (name "/GPIO35") (class "Default")
      (node (ref "J2") (pin "15") (pinfunction "15_15") (pintype "passive"))
      (node (ref "U1") (pin "31") (pinfunction "GPIO35/SPIIO6/FSPID/SUBSPID_31") (pintype "passive"))
    )
    (net (code "46") (name "/GPIO36") (class "Default")
      (node (ref "J2") (pin "14") (pinfunction "14_14") (pintype "passive"))
      (node (ref "U1") (pin "32") (pinfunction "GPIO36/SPIIO7/FSPICLK/SUBSPICLK_32") (pintype "passive"))
    )
    (net (code "47") (name "/GPIO37") (class "Default")
      (node (ref "J2") (pin "13") (pinfunction "13_13") (pintype "passive"))
      (node (ref "U1") (pin "33") (pinfunction "GPIO37/SPIDQS/FSPIQ/SUBSPIQ_33") (pintype "passive"))
    )
    (net (code "48") (name "/GPIO38") (class "Default")
      (node (ref "J2") (pin "12") (pinfunction "12_12") (pintype "passive"))
      (node (ref "U1") (pin "34") (pinfunction "GPIO38/FSPIWP/SUBSPIWP_34") (pintype "passive"))
    )
    (net (code "49") (name "/GPIO39") (class "Default")
      (node (ref "J2") (pin "11") (pinfunction "11_11") (pintype "passive"))
      (node (ref "U1") (pin "35") (pinfunction "MTCK/GPIO39/CLK_OUT3/SUBSPICS1_35") (pintype "passive"))
    )
    (net (code "50") (name "/GPIO40") (class "Default")
      (node (ref "J2") (pin "10") (pinfunction "10_10") (pintype "passive"))
      (node (ref "U1") (pin "36") (pinfunction "MTDO/GPIO40/CLK_OUT2_36") (pintype "passive"))
    )
    (net (code "51") (name "/GPIO41") (class "Default")
      (node (ref "J2") (pin "9") (pinfunction "9_9") (pintype "passive"))
      (node (ref "U1") (pin "37") (pinfunction "MTDI/GPIO41/CLK_OUT1_37") (pintype "passive"))
    )
    (net (code "52") (name "/GPIO42") (class "Default")
      (node (ref "J2") (pin "8") (pinfunction "8_8") (pintype "passive"))
      (node (ref "U1") (pin "38") (pinfunction "MTMS/GPIO42_38") (pintype "passive"))
    )
    (net (code "53") (name "/GPIO45") (class "Default")
      (node (ref "J2") (pin "5") (pinfunction "5_5") (pintype "passive"))
      (node (ref "U1") (pin "41") (pinfunction "GPIO45_41") (pintype "passive"))
    )
    (net (code "54") (name "/GPIO46") (class "Default")
      (node (ref "J2") (pin "4") (pinfunction "4_4") (pintype "passive"))
      (node (ref "U1") (pin "44") (pinfunction "GPIO46_44") (pintype "passive"))
    )
    (net (code "55") (name "/GPIO47") (class "Default")
      (node (ref "J2") (pin "23") (pinfunction "23_23") (pintype "passive"))
      (node (ref "U1") (pin "27") (pinfunction "GPIO47/SPICLK_P_DIFF/SUBSPICLK_P_DIFF_27") (pintype "passive"))
    )
    (net (code "56") (name "/GPIO48") (class "Default")
      (node (ref "J2") (pin "22") (pinfunction "22_22") (pintype "passive"))
      (node (ref "U1") (pin "30") (pinfunction "GPIO48/SPICLK_N_DIFF/SUBSPICLK_N_DIFF_30") (pintype "passive"))
    )
    (net (code "57") (name "/RTS_FTDI") (class "Default")
      (node (ref "R22") (pin "1") (pinfunction "1_1") (pintype "passive"))
      (node (ref "T1") (pin "2") (pinfunction "E_2") (pintype "passive"))
      (node (ref "U2") (pin "19") (pinfunction "~{RTS}_19") (pintype "passive"))
    )
    (net (code "58") (name "/RXD_FTDI") (class "Default")
      (node (ref "R18") (pin "2") (pinfunction "2_2") (pintype "passive"))
      (node (ref "U2") (pin "1") (pinfunction "RXD_1") (pintype "passive"))
    )
    (net (code "59") (name "/TXD_FTDI") (class "Default")
      (node (ref "R19") (pin "2") (pinfunction "2_2") (pintype "passive"))
      (node (ref "U2") (pin "17") (pinfunction "TXD_17") (pintype "passive"))
    )
    (net (code "60") (name "/U0RXD") (class "Default")
      (node (ref "J2") (pin "6") (pinfunction "6_6") (pintype "passive"))
      (node (ref "R19") (pin "1") (pinfunction "1_1") (pintype "passive"))
      (node (ref "U1") (pin "40") (pinfunction "U0RXD/GPIO44/CLK_OUT2_40") (pintype "passive"))
    )
    (net (code "61") (name "/U0TXD") (class "Default")
      (node (ref "J2") (pin "7") (pinfunction "7_7") (pintype "passive"))
      (node (ref "R18") (pin "1") (pinfunction "1_1") (pintype "passive"))
      (node (ref "U1") (pin "39") (pinfunction "U0TXD/GPIO43/CLK_OUT1_39") (pintype "passive"))
    )
    (net (code "62") (name "/VBUS_SENSE") (class "Default")
      (node (ref "R11") (pin "2") (pinfunction "2_2") (pintype "passive"))
      (node (ref "R8") (pin "1") (pinfunction "1_1") (pintype "passive"))
      (node (ref "U2") (pin "16") (pinfunction "CBUS3_16") (pintype "passive"))
    )
    (net (code "63") (name "3.3V_REG") (class "Default")
      (node (ref "C12") (pin "2") (pinfunction "2_2") (pintype "passive"))
      (node (ref "C13") (pin "2") (pinfunction "2_2") (pintype "passive"))
      (node (ref "J5") (pin "1") (pinfunction "1_1") (pintype "passive"))
      (node (ref "U3") (pin "3") (pinfunction "OUT_3") (pintype "power_in"))
    )
    (net (code "64") (name "GND") (class "Default")
      (node (ref "C1") (pin "1") (pinfunction "1_1") (pintype "passive"))
      (node (ref "C10") (pin "1") (pinfunction "1_1") (pintype "passive"))
      (node (ref "C11") (pin "1") (pinfunction "1_1") (pintype "passive"))
      (node (ref "C12") (pin "1") (pinfunction "1_1") (pintype "passive"))
      (node (ref "C13") (pin "1") (pinfunction "1_1") (pintype "passive"))
      (node (ref "C14") (pin "1") (pinfunction "1_1") (pintype "passive"))
      (node (ref "C15") (pin "1") (pinfunction "1_1") (pintype "passive"))
      (node (ref "C16") (pin "2") (pinfunction "2_2") (pintype "passive"))
      (node (ref "C17") (pin "1") (pinfunction "1_1") (pintype "passive"))
      (node (ref "C2") (pin "1") (pinfunction "1_1") (pintype "passive"))
      (node (ref "C3") (pin "1") (pinfunction "1_1") (pintype "passive"))
      (node (ref "C4") (pin "1") (pinfunction "1_1") (pintype "passive"))
      (node (ref "C5") (pin "1") (pinfunction "1_1") (pintype "passive"))
      (node (ref "C6") (pin "1") (pinfunction "1_1") (pintype "passive"))
      (node (ref "C7") (pin "1") (pinfunction "1_1") (pintype "passive"))
      (node (ref "C8") (pin "1") (pinfunction "1_1") (pintype "passive"))
      (node (ref "C9") (pin "1") (pinfunction "1_1") (pintype "passive"))
      (node (ref "D1") (pin "2") (pinfunction "2_2") (pintype "passive"))
      (node (ref "D2") (pin "2") (pinfunction "2_2") (pintype "passive"))
      (node (ref "D3") (pin "2") (pinfunction "2_2") (pintype "passive"))
      (node (ref "D4") (pin "2") (pinfunction "2_2") (pintype "passive"))
      (node (ref "D5") (pin "2") (pinfunction "2_2") (pintype "passive"))
      (node (ref "D6") (pin "2") (pinfunction "2_2") (pintype "passive"))
      (node (ref "D8") (pin "1") (pinfunction "1_1") (pintype "passive"))
      (node (ref "J1") (pin "1") (pinfunction "1_1") (pintype "passive"))
      (node (ref "J1") (pin "23") (pinfunction "23_23") (pintype "passive"))
      (node (ref "J2") (pin "2") (pinfunction "2_2") (pintype "passive"))
      (node (ref "J2") (pin "24") (pinfunction "24_24") (pintype "passive"))
      (node (ref "J3") (pin "A1B12") (pinfunction "GND_A1B12_A1B12") (pintype "passive"))
      (node (ref "J3") (pin "B1A12") (pinfunction "GND_B1A12_B1A12") (pintype "passive"))
      (node (ref "J3") (pin "S1") (pinfunction "SHEILD_1_S1") (pintype "passive"))
      (node (ref "J3") (pin "S2") (pinfunction "SHEILD_2_S2") (pintype "passive"))
      (node (ref "J3") (pin "S3") (pinfunction "SHEILD_3_S3") (pintype "passive"))
      (node (ref "J3") (pin "S4") (pinfunction "SHEILD_4_S4") (pintype "passive"))
      (node (ref "J4") (pin "A1B12") (pinfunction "GND_A1B12_A1B12") (pintype "passive"))
      (node (ref "J4") (pin "B1A12") (pinfunction "GND_B1A12_B1A12") (pintype "passive"))
      (node (ref "J4") (pin "S1") (pinfunction "SHEILD_1_S1") (pintype "passive"))
      (node (ref "J4") (pin "S2") (pinfunction "SHEILD_2_S2") (pintype "passive"))
      (node (ref "J4") (pin "S3") (pinfunction "SHEILD_3_S3") (pintype "passive"))
      (node (ref "J4") (pin "S4") (pinfunction "SHEILD_4_S4") (pintype "passive"))
      (node (ref "R10") (pin "1") (pinfunction "1_1") (pintype "passive"))
      (node (ref "R11") (pin "1") (pinfunction "1_1") (pintype "passive"))
      (node (ref "R12") (pin "1") (pinfunction "1_1") (pintype "passive"))
      (node (ref "R13") (pin "1") (pinfunction "1_1") (pintype "passive"))
      (node (ref "R7") (pin "1") (pinfunction "1_1") (pintype "passive"))
      (node (ref "R9") (pin "1") (pinfunction "1_1") (pintype "passive"))
      (node (ref "SW1") (pin "3") (pinfunction "3_3") (pintype "passive"))
      (node (ref "SW1") (pin "4") (pinfunction "4_4") (pintype "passive"))
      (node (ref "SW2") (pin "3") (pinfunction "3_3") (pintype "passive"))
      (node (ref "SW2") (pin "4") (pinfunction "4_4") (pintype "passive"))
      (node (ref "U1") (pin "1") (pinfunction "GND_01_1") (pintype "passive"))
      (node (ref "U1") (pin "2") (pinfunction "GND_02_2") (pintype "passive"))
      (node (ref "U1") (pin "42") (pinfunction "GND_42") (pintype "passive"))
      (node (ref "U1") (pin "43") (pinfunction "GND_43") (pintype "passive"))
      (node (ref "U1") (pin "46") (pinfunction "GND_46_46") (pintype "passive"))
      (node (ref "U1") (pin "47") (pinfunction "GND_47_47") (pintype "passive"))
      (node (ref "U1") (pin "48") (pinfunction "GND_48_48") (pintype "passive"))
      (node (ref "U1") (pin "49") (pinfunction "GND_49_49") (pintype "passive"))
      (node (ref "U1") (pin "50") (pinfunction "GND_50_50") (pintype "passive"))
      (node (ref "U1") (pin "51") (pinfunction "GND_51_51") (pintype "passive"))
      (node (ref "U1") (pin "52") (pinfunction "GND_52_52") (pintype "passive"))
      (node (ref "U1") (pin "53") (pinfunction "GND_53_53") (pintype "passive"))
      (node (ref "U1") (pin "54") (pinfunction "GND_54_54") (pintype "passive"))
      (node (ref "U1") (pin "55") (pinfunction "GND_55_55") (pintype "passive"))
      (node (ref "U1") (pin "56") (pinfunction "GND_56_56") (pintype "passive"))
      (node (ref "U1") (pin "57") (pinfunction "GND_57_57") (pintype "passive"))
      (node (ref "U1") (pin "58") (pinfunction "GND_58_58") (pintype "passive"))
      (node (ref "U1") (pin "59") (pinfunction "GND_59_59") (pintype "passive"))
      (node (ref "U1") (pin "60") (pinfunction "GND_60_60") (pintype "passive"))
      (node (ref "U1") (pin "61") (pinfunction "GND_61_61") (pintype "passive"))
      (node (ref "U1") (pin "62") (pinfunction "GND_62_62") (pintype "passive"))
      (node (ref "U1") (pin "63") (pinfunction "GND_63_63") (pintype "passive"))
      (node (ref "U1") (pin "64") (pinfunction "GND_64_64") (pintype "passive"))
      (node (ref "U1") (pin "65") (pinfunction "GND_65_65") (pintype "passive"))
      (node (ref "U1") (pin "66") (pinfunction "GND_66_66") (pintype "passive"))
      (node (ref "U1") (pin "67") (pinfunction "GND_67_67") (pintype "passive"))
      (node (ref "U1") (pin "68") (pinfunction "GND_68_68") (pintype "passive"))
      (node (ref "U1") (pin "69") (pinfunction "GND_69_69") (pintype "passive"))
      (node (ref "U1") (pin "70") (pinfunction "GND_70_70") (pintype "passive"))
      (node (ref "U1") (pin "71") (pinfunction "GND_71_71") (pintype "passive"))
      (node (ref "U1") (pin "72") (pinfunction "GND_72_72") (pintype "passive"))
      (node (ref "U1") (pin "73") (pinfunction "GND_73_73") (pintype "passive"))
      (node (ref "U2") (pin "13") (pinfunction "GND_13") (pintype "passive"))
      (node (ref "U2") (pin "21") (pinfunction "GND_21") (pintype "passive"))
      (node (ref "U2") (pin "3") (pinfunction "GND_3") (pintype "passive"))
      (node (ref "U3") (pin "2") (pinfunction "GND_2") (pintype "power_in"))
      (node (ref "U3") (pin "4") (pinfunction "GND_4") (pintype "power_in"))
    )
    (net (code "65") (name "Net-(D7-Pad2)") (class "Default")
      (node (ref "D7") (pin "2") (pinfunction "2_2") (pintype "passive"))
      (node (ref "R15") (pin "1") (pinfunction "1_1") (pintype "passive"))
    )
    (net (code "66") (name "Net-(D8-Pad2)") (class "Default")
      (node (ref "D8") (pin "2") (pinfunction "2_2") (pintype "passive"))
      (node (ref "R14") (pin "1") (pinfunction "1_1") (pintype "passive"))
    )
    (net (code "67") (name "Net-(J3-CC1)") (class "Default")
      (node (ref "J3") (pin "A5") (pinfunction "CC1_A5") (pintype "passive"))
      (node (ref "R10") (pin "2") (pinfunction "2_2") (pintype "passive"))
    )
    (net (code "68") (name "Net-(J3-CC2)") (class "Default")
      (node (ref "J3") (pin "B5") (pinfunction "CC2_B5") (pintype "passive"))
      (node (ref "R9") (pin "2") (pinfunction "2_2") (pintype "passive"))
    )
    (net (code "69") (name "Net-(J4-CC1)") (class "Default")
      (node (ref "J4") (pin "A5") (pinfunction "CC1_A5") (pintype "passive"))
      (node (ref "R13") (pin "2") (pinfunction "2_2") (pintype "passive"))
    )
    (net (code "70") (name "Net-(J4-CC2)") (class "Default")
      (node (ref "J4") (pin "B5") (pinfunction "CC2_B5") (pintype "passive"))
      (node (ref "R12") (pin "2") (pinfunction "2_2") (pintype "passive"))
    )
    (net (code "71") (name "Net-(T1-B)") (class "Default")
      (node (ref "R17") (pin "1") (pinfunction "1_1") (pintype "passive"))
      (node (ref "T1") (pin "1") (pinfunction "B_1") (pintype "passive"))
    )
    (net (code "72") (name "Net-(T2-B)") (class "Default")
      (node (ref "R22") (pin "2") (pinfunction "2_2") (pintype "passive"))
      (node (ref "T2") (pin "1") (pinfunction "B_1") (pintype "passive"))
    )
    (net (code "73") (name "Net-(U2-CBUS0)") (class "Default")
      (node (ref "R7") (pin "2") (pinfunction "2_2") (pintype "passive"))
      (node (ref "U2") (pin "15") (pinfunction "CBUS0_15") (pintype "passive"))
    )
    (net (code "74") (name "unconnected-(J1-Pad24)") (class "Default")
      (node (ref "J1") (pin "24") (pinfunction "24_24") (pintype "passive"))
    )
    (net (code "75") (name "unconnected-(J3-SBU1-PadA8)") (class "Default")
      (node (ref "J3") (pin "A8") (pinfunction "SBU1_A8") (pintype "passive+no_connect"))
    )
    (net (code "76") (name "unconnected-(J3-SBU2-PadB8)") (class "Default")
      (node (ref "J3") (pin "B8") (pinfunction "SBU2_B8") (pintype "passive+no_connect"))
    )
    (net (code "77") (name "unconnected-(J4-SBU1-PadA8)") (class "Default")
      (node (ref "J4") (pin "A8") (pinfunction "SBU1_A8") (pintype "passive+no_connect"))
    )
    (net (code "78") (name "unconnected-(J4-SBU2-PadB8)") (class "Default")
      (node (ref "J4") (pin "B8") (pinfunction "SBU2_B8") (pintype "passive+no_connect"))
    )
    (net (code "79") (name "unconnected-(U2-CBUS1-Pad14)") (class "Default")
      (node (ref "U2") (pin "14") (pinfunction "CBUS1_14") (pintype "passive+no_connect"))
    )
    (net (code "80") (name "unconnected-(U2-CBUS2-Pad7)") (class "Default")
      (node (ref "U2") (pin "7") (pinfunction "CBUS2_7") (pintype "passive+no_connect"))
    )
    (net (code "81") (name "unconnected-(U2-~{CTS}-Pad6)") (class "Default")
      (node (ref "U2") (pin "6") (pinfunction "~{CTS}_6") (pintype "passive+no_connect"))
    )
    (net (code "82") (name "unconnected-(U2-~{DCD}-Pad5)") (class "Default")
      (node (ref "U2") (pin "5") (pinfunction "~{DCD}_5") (pintype "passive+no_connect"))
    )
    (net (code "83") (name "unconnected-(U2-~{DSR}-Pad4)") (class "Default")
      (node (ref "U2") (pin "4") (pinfunction "~{DSR}_4") (pintype "passive+no_connect"))
    )
    (net (code "84") (name "unconnected-(U2-~{RI}-Pad2)") (class "Default")
      (node (ref "U2") (pin "2") (pinfunction "~{RI}_2") (pintype "passive+no_connect"))
    )
  )
)
